# data_board_with_PD.net
KiCad netlist of a schematic drawn in EAGLE
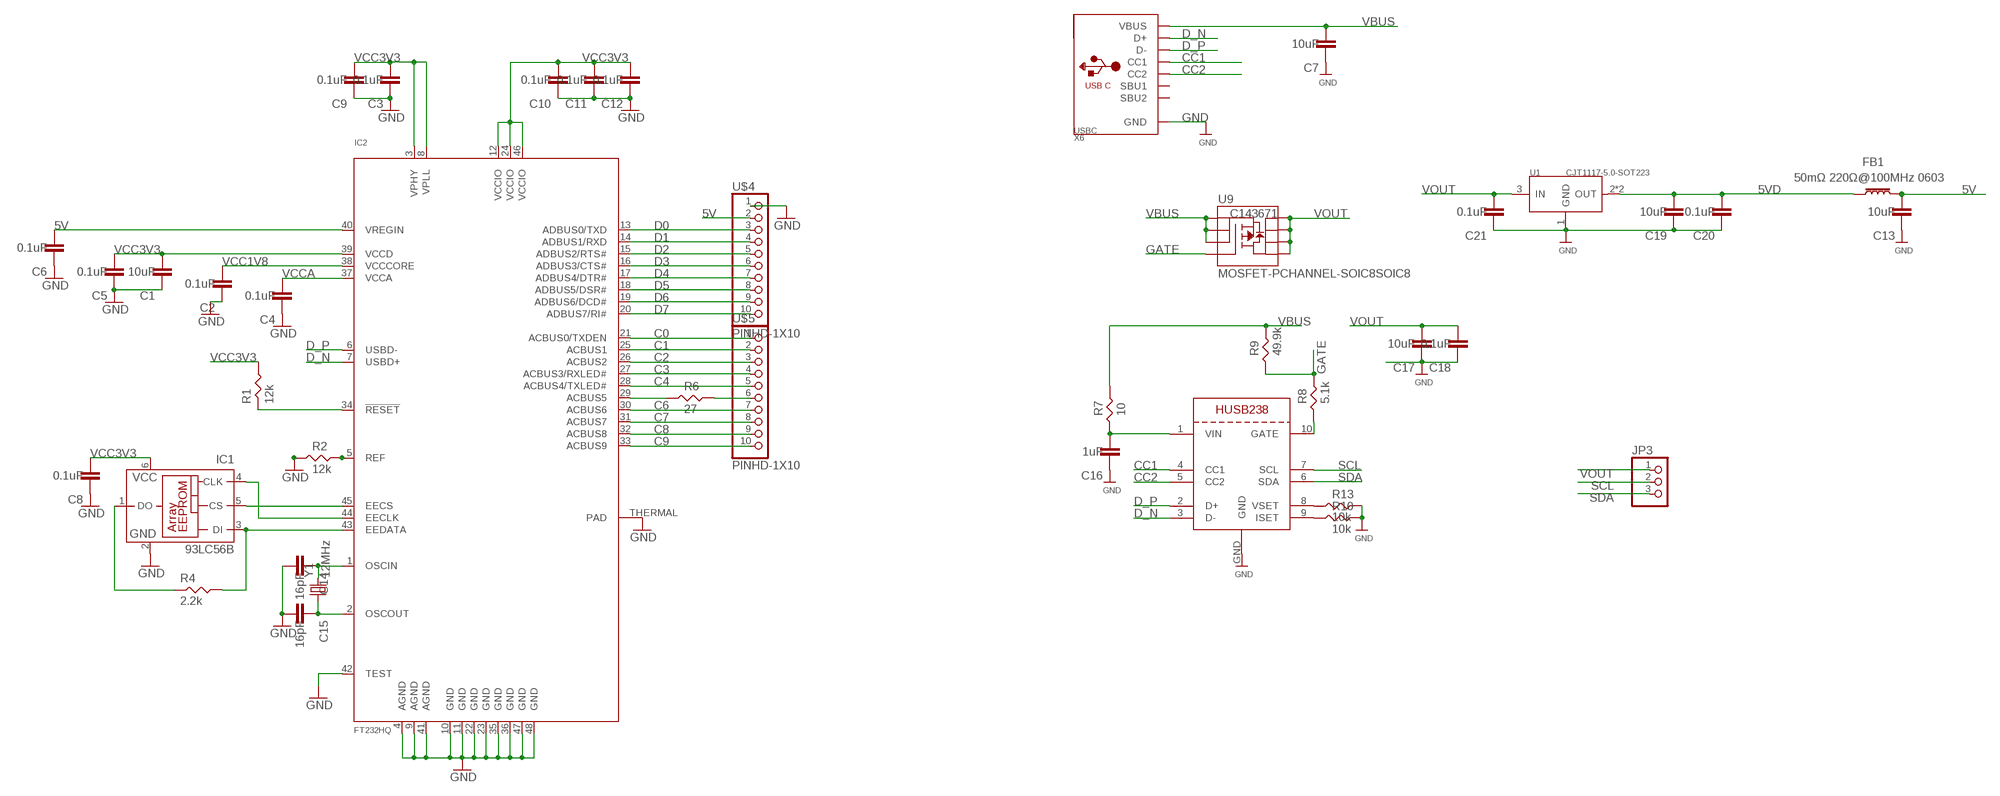
[diagram p0: schematic, sheet 1]

(export (version "E")
  (design (tool "Eeschema 10.0.6"))
  (components
    (comp (ref "C1")
      (value "10uF")
      (footprint "eagle-import:RESC0805_N")
      (libsource (lib "eagle-import") (part "CAPACITOR_0805_N"))
    )
    (comp (ref "C2")
      (value "0.1uF")
      (footprint "eagle-import:RESC0402_N")
      (libsource (lib "eagle-import") (part "CAPACITOR_0402_N"))
    )
    (comp (ref "C3")
      (value "0.1uF")
      (footprint "eagle-import:RESC0402_N")
      (libsource (lib "eagle-import") (part "CAPACITOR_0402_N"))
    )
    (comp (ref "C4")
      (value "0.1uF")
      (footprint "eagle-import:RESC0402_N")
      (libsource (lib "eagle-import") (part "CAPACITOR_0402_N"))
    )
    (comp (ref "C5")
      (value "0.1uF")
      (footprint "eagle-import:RESC0402_N")
      (libsource (lib "eagle-import") (part "CAPACITOR_0402_N"))
    )
    (comp (ref "C6")
      (value "0.1uF")
      (footprint "eagle-import:RESC0402_N")
      (libsource (lib "eagle-import") (part "CAPACITOR_0402_N"))
    )
    (comp (ref "C7")
      (value "10uF")
      (footprint "eagle-import:RESC0805_N")
      (libsource (lib "eagle-import") (part "CAPACITOR_0805_N"))
    )
    (comp (ref "C8")
      (value "0.1uF")
      (footprint "eagle-import:RESC0402_N")
      (libsource (lib "eagle-import") (part "CAPACITOR_0402_N"))
    )
    (comp (ref "C9")
      (value "0.1uF")
      (footprint "eagle-import:RESC0402_N")
      (libsource (lib "eagle-import") (part "CAPACITOR_0402_N"))
    )
    (comp (ref "C10")
      (value "0.1uF")
      (footprint "eagle-import:RESC0402_N")
      (libsource (lib "eagle-import") (part "CAPACITOR_0402_N"))
    )
    (comp (ref "C11")
      (value "0.1uF")
      (footprint "eagle-import:RESC0402_N")
      (libsource (lib "eagle-import") (part "CAPACITOR_0402_N"))
    )
    (comp (ref "C12")
      (value "0.1uF")
      (footprint "eagle-import:RESC0402_N")
      (libsource (lib "eagle-import") (part "CAPACITOR_0402_N"))
    )
    (comp (ref "C13")
      (value "10uF")
      (footprint "eagle-import:RESC0805_N")
      (libsource (lib "eagle-import") (part "CAPACITOR_0805_N"))
    )
    (comp (ref "C14")
      (value "16pF")
      (footprint "eagle-import:RESC0402_N")
      (libsource (lib "eagle-import") (part "CAPACITOR_0402_N"))
    )
    (comp (ref "C15")
      (value "16pF")
      (footprint "eagle-import:RESC0402_N")
      (libsource (lib "eagle-import") (part "CAPACITOR_0402_N"))
    )
    (comp (ref "C16")
      (value "1uF")
      (footprint "eagle-import:RESC0402_N")
      (libsource (lib "eagle-import") (part "CAPACITOR_0402_N"))
    )
    (comp (ref "C17")
      (value "10uF")
      (footprint "eagle-import:RESC0805_N")
      (libsource (lib "eagle-import") (part "CAPACITOR_0805_N"))
    )
    (comp (ref "C18")
      (value "0.1uF")
      (footprint "eagle-import:RESC0402_N")
      (libsource (lib "eagle-import") (part "CAPACITOR_0402_N"))
    )
    (comp (ref "C19")
      (value "10uF")
      (footprint "eagle-import:RESC0805_N")
      (libsource (lib "eagle-import") (part "CAPACITOR_0805_N"))
    )
    (comp (ref "C20")
      (value "0.1uF")
      (footprint "eagle-import:RESC0402_N")
      (libsource (lib "eagle-import") (part "CAPACITOR_0402_N"))
    )
    (comp (ref "C21")
      (value "0.1uF")
      (footprint "eagle-import:RESC0402_N")
      (libsource (lib "eagle-import") (part "CAPACITOR_0402_N"))
    )
    (comp (ref "FB1")
      (value "50mΩ 220Ω@100MHz 0603")
      (footprint "eagle-import:0603")
      (libsource (lib "eagle-import") (part "FERRITE_BEAD-0603"))
    )
    (comp (ref "IC1")
      (value "93LC56B")
      (footprint "eagle-import:SOT23-6")
      (fields (field (name "MF") "MICROCHIP") (field (name "MPN") "93LC76AT-I/OT"))
      (libsource (lib "eagle-import") (part "9376?ALC"))
    )
    (comp (ref "IC2")
      (value "FT232HQ")
      (footprint "eagle-import:QFN48_8MM")
      (libsource (lib "eagle-import") (part "FT232HQ"))
    )
    (comp (ref "JP3")
      (value "HEADER-1X3ROUND")
      (footprint "eagle-import:1X03_ROUND")
      (libsource (lib "eagle-import") (part "HEADER-1X3ROUND"))
    )
    (comp (ref "R1")
      (value "12k")
      (footprint "eagle-import:RES-0402")
      (libsource (lib "eagle-import") (part "RES-0402"))
    )
    (comp (ref "R2")
      (value "12k")
      (footprint "eagle-import:RES-0402")
      (libsource (lib "eagle-import") (part "RES-0402"))
    )
    (comp (ref "R4")
      (value "2.2k")
      (footprint "eagle-import:RES-0402")
      (libsource (lib "eagle-import") (part "RES-0402"))
    )
    (comp (ref "R6")
      (value "27")
      (footprint "eagle-import:RES-0402")
      (libsource (lib "eagle-import") (part "RES-0402"))
    )
    (comp (ref "R7")
      (value "10")
      (footprint "eagle-import:RES-0402")
      (libsource (lib "eagle-import") (part "RES-0402"))
    )
    (comp (ref "R8")
      (value "5.1k")
      (footprint "eagle-import:RES-0402")
      (libsource (lib "eagle-import") (part "RES-0402"))
    )
    (comp (ref "R9")
      (value "49.9k")
      (footprint "eagle-import:RES-0402")
      (libsource (lib "eagle-import") (part "RES-0402"))
    )
    (comp (ref "R10")
      (value "10k")
      (footprint "eagle-import:RES-0402")
      (libsource (lib "eagle-import") (part "RES-0402"))
    )
    (comp (ref "R13")
      (value "10k")
      (footprint "eagle-import:RES-0402")
      (libsource (lib "eagle-import") (part "RES-0402"))
    )
    (comp (ref "U$4")
      (value "PINHD-1X10")
      (footprint "eagle-import:1X10-BIG")
      (libsource (lib "eagle-import") (part "PINHD-1X10"))
    )
    (comp (ref "U$5")
      (value "PINHD-1X10")
      (footprint "eagle-import:1X10-BIG")
      (libsource (lib "eagle-import") (part "PINHD-1X10"))
    )
    (comp (ref "U1")
      (value "CJT1117-5.0-SOT223")
      (footprint "eagle-import:SOT-223")
      (fields (field (name "MPN") "CJT1117-5.0"))
      (libsource (lib "eagle-import") (part "PMIC-CJT1117-5.0(SOT223)"))
    )
    (comp (ref "U9")
      (value "MOSFET-PCHANNEL-SOIC8SOIC8")
      (footprint "eagle-import:SO08")
      (fields (field (name "LCSC") "C143671"))
      (libsource (lib "eagle-import") (part "MOSFET-PCHANNEL-SOIC8SOIC8"))
    )
    (comp (ref "X3")
      (value "HUSB238")
      (footprint "eagle-import:DFN10_3X3MM")
      (libsource (lib "eagle-import") (part "HUSB238"))
    )
    (comp (ref "X6")
      (value "USBC")
      (footprint "eagle-import:USB_C_CUSB31-CFM2AX-01-X")
      (libsource (lib "eagle-import") (part "USB_C"))
    )
    (comp (ref "Y1")
      (value "12MHz")
      (footprint "eagle-import:CRYSTAL-SMD-5X3")
      (libsource (lib "eagle-import") (part "CRYSTALCRYSTAL-SMD-5X3-12MHZ"))
    )
  )
  (nets
    (net (code "1") (name "/5V") (class "Default")
      (node (ref "C13") (pin "2") (pinfunction "2_2") (pintype "passive"))
      (node (ref "C6") (pin "2") (pinfunction "2_2") (pintype "passive"))
      (node (ref "FB1") (pin "2") (pinfunction "2_2") (pintype "passive"))
      (node (ref "IC2") (pin "40") (pinfunction "VREGIN_40") (pintype "power_in"))
      (node (ref "U$4") (pin "2") (pinfunction "2_2") (pintype "passive"))
    )
    (net (code "2") (name "/5VD") (class "Default")
      (node (ref "C19") (pin "2") (pinfunction "2_2") (pintype "passive"))
      (node (ref "C20") (pin "2") (pinfunction "2_2") (pintype "passive"))
      (node (ref "FB1") (pin "1") (pinfunction "1_1") (pintype "passive"))
      (node (ref "U1") (pin "2") (pinfunction "OUT_2") (pintype "bidirectional"))
      (node (ref "U1") (pin "TER") (pinfunction "OUT_TER") (pintype "bidirectional"))
    )
    (net (code "3") (name "/C0") (class "Default")
      (node (ref "IC2") (pin "21") (pinfunction "ACBUS0/TXDEN_21") (pintype "bidirectional"))
      (node (ref "U$5") (pin "1") (pinfunction "1_1") (pintype "passive"))
    )
    (net (code "4") (name "/C1") (class "Default")
      (node (ref "IC2") (pin "25") (pinfunction "ACBUS1_25") (pintype "bidirectional"))
      (node (ref "U$5") (pin "2") (pinfunction "2_2") (pintype "passive"))
    )
    (net (code "5") (name "/C2") (class "Default")
      (node (ref "IC2") (pin "26") (pinfunction "ACBUS2_26") (pintype "bidirectional"))
      (node (ref "U$5") (pin "3") (pinfunction "3_3") (pintype "passive"))
    )
    (net (code "6") (name "/C3") (class "Default")
      (node (ref "IC2") (pin "27") (pinfunction "ACBUS3/RXLED#_27") (pintype "bidirectional"))
      (node (ref "U$5") (pin "4") (pinfunction "4_4") (pintype "passive"))
    )
    (net (code "7") (name "/C4") (class "Default")
      (node (ref "IC2") (pin "28") (pinfunction "ACBUS4/TXLED#_28") (pintype "bidirectional"))
      (node (ref "U$5") (pin "5") (pinfunction "5_5") (pintype "passive"))
    )
    (net (code "8") (name "/C6") (class "Default")
      (node (ref "IC2") (pin "30") (pinfunction "ACBUS6_30") (pintype "bidirectional"))
      (node (ref "U$5") (pin "7") (pinfunction "7_7") (pintype "passive"))
    )
    (net (code "9") (name "/C7") (class "Default")
      (node (ref "IC2") (pin "31") (pinfunction "ACBUS7_31") (pintype "bidirectional"))
      (node (ref "U$5") (pin "8") (pinfunction "8_8") (pintype "passive"))
    )
    (net (code "10") (name "/C8") (class "Default")
      (node (ref "IC2") (pin "32") (pinfunction "ACBUS8_32") (pintype "bidirectional"))
      (node (ref "U$5") (pin "9") (pinfunction "9_9") (pintype "passive"))
    )
    (net (code "11") (name "/C9") (class "Default")
      (node (ref "IC2") (pin "33") (pinfunction "ACBUS9_33") (pintype "bidirectional"))
      (node (ref "U$5") (pin "10") (pinfunction "10_10") (pintype "passive"))
    )
    (net (code "12") (name "/CC1") (class "Default")
      (node (ref "X3") (pin "4") (pinfunction "CC1_4") (pintype "input"))
      (node (ref "X6") (pin "A5") (pinfunction "CC1_A5") (pintype "bidirectional"))
    )
    (net (code "13") (name "/CC2") (class "Default")
      (node (ref "X3") (pin "5") (pinfunction "CC2_5") (pintype "input"))
      (node (ref "X6") (pin "B5") (pinfunction "CC2_B5") (pintype "bidirectional"))
    )
    (net (code "14") (name "/D0") (class "Default")
      (node (ref "IC2") (pin "13") (pinfunction "ADBUS0/TXD_13") (pintype "output"))
      (node (ref "U$4") (pin "3") (pinfunction "3_3") (pintype "passive"))
    )
    (net (code "15") (name "/D1") (class "Default")
      (node (ref "IC2") (pin "14") (pinfunction "ADBUS1/RXD_14") (pintype "input"))
      (node (ref "U$4") (pin "4") (pinfunction "4_4") (pintype "passive"))
    )
    (net (code "16") (name "/D2") (class "Default")
      (node (ref "IC2") (pin "15") (pinfunction "ADBUS2/RTS#_15") (pintype "output"))
      (node (ref "U$4") (pin "5") (pinfunction "5_5") (pintype "passive"))
    )
    (net (code "17") (name "/D3") (class "Default")
      (node (ref "IC2") (pin "16") (pinfunction "ADBUS3/CTS#_16") (pintype "input"))
      (node (ref "U$4") (pin "6") (pinfunction "6_6") (pintype "passive"))
    )
    (net (code "18") (name "/D4") (class "Default")
      (node (ref "IC2") (pin "17") (pinfunction "ADBUS4/DTR#_17") (pintype "output"))
      (node (ref "U$4") (pin "7") (pinfunction "7_7") (pintype "passive"))
    )
    (net (code "19") (name "/D5") (class "Default")
      (node (ref "IC2") (pin "18") (pinfunction "ADBUS5/DSR#_18") (pintype "input"))
      (node (ref "U$4") (pin "8") (pinfunction "8_8") (pintype "passive"))
    )
    (net (code "20") (name "/D6") (class "Default")
      (node (ref "IC2") (pin "19") (pinfunction "ADBUS6/DCD#_19") (pintype "input"))
      (node (ref "U$4") (pin "9") (pinfunction "9_9") (pintype "passive"))
    )
    (net (code "21") (name "/D7") (class "Default")
      (node (ref "IC2") (pin "20") (pinfunction "ADBUS7/RI#_20") (pintype "input"))
      (node (ref "U$4") (pin "10") (pinfunction "10_10") (pintype "passive"))
    )
    (net (code "22") (name "/D_N") (class "Default")
      (node (ref "IC2") (pin "7") (pinfunction "USBD+_7") (pintype "bidirectional"))
      (node (ref "X3") (pin "3") (pinfunction "D-_3") (pintype "input"))
      (node (ref "X6") (pin "A6") (pinfunction "D+_A6") (pintype "bidirectional"))
      (node (ref "X6") (pin "B6") (pinfunction "D+_B6") (pintype "bidirectional"))
    )
    (net (code "23") (name "/D_P") (class "Default")
      (node (ref "IC2") (pin "6") (pinfunction "USBD-_6") (pintype "bidirectional"))
      (node (ref "X3") (pin "2") (pinfunction "D+_2") (pintype "input"))
      (node (ref "X6") (pin "A7") (pinfunction "D-_A7") (pintype "bidirectional"))
      (node (ref "X6") (pin "B7") (pinfunction "D-_B7") (pintype "bidirectional"))
    )
    (net (code "24") (name "/GATE") (class "Default")
      (node (ref "R8") (pin "P$2") (pinfunction "P$2_P$2") (pintype "bidirectional"))
      (node (ref "R9") (pin "P$1") (pinfunction "P$1_P$1") (pintype "bidirectional"))
      (node (ref "U9") (pin "4") (pinfunction "G_4") (pintype "bidirectional"))
    )
    (net (code "25") (name "/SCL") (class "Default")
      (node (ref "JP3") (pin "2") (pinfunction "2_2") (pintype "passive"))
      (node (ref "X3") (pin "7") (pinfunction "SCL_7") (pintype "bidirectional"))
    )
    (net (code "26") (name "/SDA") (class "Default")
      (node (ref "JP3") (pin "3") (pinfunction "3_3") (pintype "passive"))
      (node (ref "X3") (pin "6") (pinfunction "SDA_6") (pintype "bidirectional"))
    )
    (net (code "27") (name "/VBUS") (class "Default")
      (node (ref "C7") (pin "2") (pinfunction "2_2") (pintype "passive"))
      (node (ref "R7") (pin "P$2") (pinfunction "P$2_P$2") (pintype "bidirectional"))
      (node (ref "R9") (pin "P$2") (pinfunction "P$2_P$2") (pintype "bidirectional"))
      (node (ref "U9") (pin "1") (pinfunction "S_1") (pintype "bidirectional"))
      (node (ref "U9") (pin "2") (pinfunction "S_2") (pintype "bidirectional"))
      (node (ref "U9") (pin "3") (pinfunction "S_3") (pintype "bidirectional"))
      (node (ref "X6") (pin "A4B9") (pinfunction "VBUS_A4B9") (pintype "power_in"))
      (node (ref "X6") (pin "B4A9") (pinfunction "VBUS_B4A9") (pintype "power_in"))
    )
    (net (code "28") (name "/VCC1V8") (class "Default")
      (node (ref "C2") (pin "2") (pinfunction "2_2") (pintype "passive"))
      (node (ref "IC2") (pin "38") (pinfunction "VCCCORE_38") (pintype "power_in"))
    )
    (net (code "29") (name "/VCC3V3") (class "Default")
      (node (ref "C1") (pin "2") (pinfunction "2_2") (pintype "passive"))
      (node (ref "C10") (pin "2") (pinfunction "2_2") (pintype "passive"))
      (node (ref "C11") (pin "2") (pinfunction "2_2") (pintype "passive"))
      (node (ref "C12") (pin "2") (pinfunction "2_2") (pintype "passive"))
      (node (ref "C3") (pin "2") (pinfunction "2_2") (pintype "passive"))
      (node (ref "C5") (pin "2") (pinfunction "2_2") (pintype "passive"))
      (node (ref "C8") (pin "2") (pinfunction "2_2") (pintype "passive"))
      (node (ref "C9") (pin "2") (pinfunction "2_2") (pintype "passive"))
      (node (ref "IC1") (pin "6") (pinfunction "VCC_6") (pintype "power_in"))
      (node (ref "IC2") (pin "12") (pinfunction "VCCIO_12") (pintype "power_in"))
      (node (ref "IC2") (pin "24") (pinfunction "VCCIO_24") (pintype "power_in"))
      (node (ref "IC2") (pin "3") (pinfunction "VPHY_3") (pintype "power_in"))
      (node (ref "IC2") (pin "39") (pinfunction "VCCD_39") (pintype "power_in"))
      (node (ref "IC2") (pin "46") (pinfunction "VCCIO_46") (pintype "power_in"))
      (node (ref "IC2") (pin "8") (pinfunction "VPLL_8") (pintype "power_in"))
      (node (ref "R1") (pin "P$2") (pinfunction "P$2_P$2") (pintype "bidirectional"))
    )
    (net (code "30") (name "/VCCA") (class "Default")
      (node (ref "C4") (pin "2") (pinfunction "2_2") (pintype "passive"))
      (node (ref "IC2") (pin "37") (pinfunction "VCCA_37") (pintype "power_in"))
    )
    (net (code "31") (name "/VOUT") (class "Default")
      (node (ref "C17") (pin "2") (pinfunction "2_2") (pintype "passive"))
      (node (ref "C18") (pin "2") (pinfunction "2_2") (pintype "passive"))
      (node (ref "C21") (pin "2") (pinfunction "2_2") (pintype "passive"))
      (node (ref "JP3") (pin "1") (pinfunction "1_1") (pintype "passive"))
      (node (ref "U1") (pin "3") (pinfunction "IN_3") (pintype "bidirectional"))
      (node (ref "U9") (pin "5") (pinfunction "D_5") (pintype "bidirectional"))
      (node (ref "U9") (pin "6") (pinfunction "D_6") (pintype "bidirectional"))
      (node (ref "U9") (pin "7") (pinfunction "D_7") (pintype "bidirectional"))
      (node (ref "U9") (pin "8") (pinfunction "D_8") (pintype "bidirectional"))
    )
    (net (code "32") (name "GND") (class "Default")
      (node (ref "C1") (pin "1") (pinfunction "1_1") (pintype "passive"))
      (node (ref "C10") (pin "1") (pinfunction "1_1") (pintype "passive"))
      (node (ref "C11") (pin "1") (pinfunction "1_1") (pintype "passive"))
      (node (ref "C12") (pin "1") (pinfunction "1_1") (pintype "passive"))
      (node (ref "C13") (pin "1") (pinfunction "1_1") (pintype "passive"))
      (node (ref "C14") (pin "2") (pinfunction "2_2") (pintype "passive"))
      (node (ref "C15") (pin "2") (pinfunction "2_2") (pintype "passive"))
      (node (ref "C16") (pin "1") (pinfunction "1_1") (pintype "passive"))
      (node (ref "C17") (pin "1") (pinfunction "1_1") (pintype "passive"))
      (node (ref "C18") (pin "1") (pinfunction "1_1") (pintype "passive"))
      (node (ref "C19") (pin "1") (pinfunction "1_1") (pintype "passive"))
      (node (ref "C2") (pin "1") (pinfunction "1_1") (pintype "passive"))
      (node (ref "C20") (pin "1") (pinfunction "1_1") (pintype "passive"))
      (node (ref "C21") (pin "1") (pinfunction "1_1") (pintype "passive"))
      (node (ref "C3") (pin "1") (pinfunction "1_1") (pintype "passive"))
      (node (ref "C4") (pin "1") (pinfunction "1_1") (pintype "passive"))
      (node (ref "C5") (pin "1") (pinfunction "1_1") (pintype "passive"))
      (node (ref "C6") (pin "1") (pinfunction "1_1") (pintype "passive"))
      (node (ref "C7") (pin "1") (pinfunction "1_1") (pintype "passive"))
      (node (ref "C8") (pin "1") (pinfunction "1_1") (pintype "passive"))
      (node (ref "C9") (pin "1") (pinfunction "1_1") (pintype "passive"))
      (node (ref "IC1") (pin "2") (pinfunction "GND_2") (pintype "power_in"))
      (node (ref "IC2") (pin "10") (pinfunction "GND_10") (pintype "power_in"))
      (node (ref "IC2") (pin "11") (pinfunction "GND_11") (pintype "power_in"))
      (node (ref "IC2") (pin "22") (pinfunction "GND_22") (pintype "power_in"))
      (node (ref "IC2") (pin "23") (pinfunction "GND_23") (pintype "power_in"))
      (node (ref "IC2") (pin "35") (pinfunction "GND_35") (pintype "power_in"))
      (node (ref "IC2") (pin "36") (pinfunction "GND_36") (pintype "power_in"))
      (node (ref "IC2") (pin "4") (pinfunction "AGND_4") (pintype "power_in"))
      (node (ref "IC2") (pin "41") (pinfunction "AGND_41") (pintype "power_in"))
      (node (ref "IC2") (pin "42") (pinfunction "TEST_42") (pintype "input"))
      (node (ref "IC2") (pin "47") (pinfunction "GND_47") (pintype "power_in"))
      (node (ref "IC2") (pin "48") (pinfunction "GND_48") (pintype "power_in"))
      (node (ref "IC2") (pin "9") (pinfunction "AGND_9") (pintype "power_in"))
      (node (ref "IC2") (pin "THERMAL") (pinfunction "PAD_THERMAL") (pintype "passive"))
      (node (ref "R10") (pin "P$2") (pinfunction "P$2_P$2") (pintype "bidirectional"))
      (node (ref "R13") (pin "P$2") (pinfunction "P$2_P$2") (pintype "bidirectional"))
      (node (ref "R2") (pin "P$1") (pinfunction "P$1_P$1") (pintype "bidirectional"))
      (node (ref "U$4") (pin "1") (pinfunction "1_1") (pintype "passive"))
      (node (ref "U1") (pin "1") (pinfunction "GND_1") (pintype "bidirectional"))
      (node (ref "X3") (pin "GND") (pinfunction "GND_GND") (pintype "power_in"))
      (node (ref "X6") (pin "A1B12") (pinfunction "GND_A1B12") (pintype "power_in"))
      (node (ref "X6") (pin "B1A12") (pinfunction "GND_B1A12") (pintype "power_in"))
    )
    (net (code "33") (name "Net-(IC1-CLK)") (class "Default")
      (node (ref "IC1") (pin "4") (pinfunction "CLK_4") (pintype "input"))
      (node (ref "IC2") (pin "44") (pinfunction "EECLK_44") (pintype "output"))
    )
    (net (code "34") (name "Net-(IC1-CS)") (class "Default")
      (node (ref "IC1") (pin "5") (pinfunction "CS_5") (pintype "input"))
      (node (ref "IC2") (pin "45") (pinfunction "EECS_45") (pintype "bidirectional"))
    )
    (net (code "35") (name "Net-(IC1-DI)") (class "Default")
      (node (ref "IC1") (pin "3") (pinfunction "DI_3") (pintype "input"))
      (node (ref "IC2") (pin "43") (pinfunction "EEDATA_43") (pintype "bidirectional"))
      (node (ref "R4") (pin "P$2") (pinfunction "P$2_P$2") (pintype "bidirectional"))
    )
    (net (code "36") (name "Net-(IC1-DO)") (class "Default")
      (node (ref "IC1") (pin "1") (pinfunction "DO_1") (pintype "tri_state"))
      (node (ref "R4") (pin "P$1") (pinfunction "P$1_P$1") (pintype "bidirectional"))
    )
    (net (code "37") (name "Net-(IC2-ACBUS5)") (class "Default")
      (node (ref "IC2") (pin "29") (pinfunction "ACBUS5_29") (pintype "bidirectional"))
      (node (ref "R6") (pin "P$1") (pinfunction "P$1_P$1") (pintype "bidirectional"))
    )
    (net (code "38") (name "Net-(IC2-OSCIN)") (class "Default")
      (node (ref "C14") (pin "1") (pinfunction "1_1") (pintype "passive"))
      (node (ref "IC2") (pin "1") (pinfunction "OSCIN_1") (pintype "input"))
      (node (ref "Y1") (pin "3") (pinfunction "2_3") (pintype "passive"))
    )
    (net (code "39") (name "Net-(IC2-OSCOUT)") (class "Default")
      (node (ref "C15") (pin "1") (pinfunction "1_1") (pintype "passive"))
      (node (ref "IC2") (pin "2") (pinfunction "OSCOUT_2") (pintype "output"))
      (node (ref "Y1") (pin "1") (pinfunction "1_1") (pintype "passive"))
    )
    (net (code "40") (name "Net-(IC2-REF)") (class "Default")
      (node (ref "IC2") (pin "5") (pinfunction "REF_5") (pintype "input"))
      (node (ref "R2") (pin "P$2") (pinfunction "P$2_P$2") (pintype "bidirectional"))
    )
    (net (code "41") (name "Net-(IC2-~{RESET})") (class "Default")
      (node (ref "IC2") (pin "34") (pinfunction "~{RESET}_34") (pintype "input"))
      (node (ref "R1") (pin "P$1") (pinfunction "P$1_P$1") (pintype "bidirectional"))
    )
    (net (code "42") (name "Net-(R6-PadP$2)") (class "Default")
      (node (ref "R6") (pin "P$2") (pinfunction "P$2_P$2") (pintype "bidirectional"))
      (node (ref "U$5") (pin "6") (pinfunction "6_6") (pintype "passive"))
    )
    (net (code "43") (name "Net-(X3-GATE)") (class "Default")
      (node (ref "R8") (pin "P$1") (pinfunction "P$1_P$1") (pintype "bidirectional"))
      (node (ref "X3") (pin "10") (pinfunction "GATE_10") (pintype "output"))
    )
    (net (code "44") (name "Net-(X3-ISET)") (class "Default")
      (node (ref "R10") (pin "P$1") (pinfunction "P$1_P$1") (pintype "bidirectional"))
      (node (ref "X3") (pin "9") (pinfunction "ISET_9") (pintype "passive"))
    )
    (net (code "45") (name "Net-(X3-VIN)") (class "Default")
      (node (ref "C16") (pin "2") (pinfunction "2_2") (pintype "passive"))
      (node (ref "R7") (pin "P$1") (pinfunction "P$1_P$1") (pintype "bidirectional"))
      (node (ref "X3") (pin "1") (pinfunction "VIN_1") (pintype "power_in"))
    )
    (net (code "46") (name "Net-(X3-VSET)") (class "Default")
      (node (ref "R13") (pin "P$1") (pinfunction "P$1_P$1") (pintype "bidirectional"))
      (node (ref "X3") (pin "8") (pinfunction "VSET_8") (pintype "passive"))
    )
    (net (code "47") (name "unconnected-(X6-SBU1-PadA8)") (class "Default")
      (node (ref "X6") (pin "A8") (pinfunction "SBU1_A8") (pintype "bidirectional"))
    )
    (net (code "48") (name "unconnected-(X6-SBU2-PadB8)") (class "Default")
      (node (ref "X6") (pin "B8") (pinfunction "SBU2_B8") (pintype "bidirectional"))
    )
  )
)
